# UltrasonicSensor.net
KiCad netlist of a schematic drawn in EAGLE
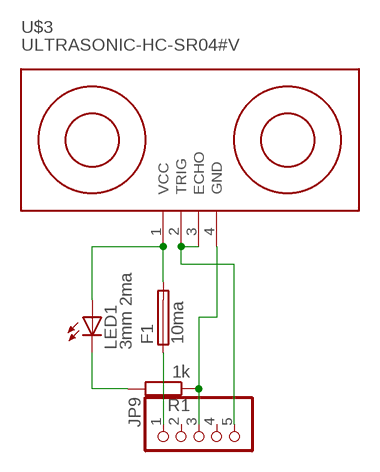
[diagram p0: schematic, sheet 1]

(export (version "E")
  (design (tool "Eeschema 10.0.6"))
  (components
    (comp (ref "F1")
      (value "10ma")
      (footprint "eagle-import:MF-SMDF050")
      (libsource (lib "eagle-import") (part "MF-SMDF050"))
    )
    (comp (ref "JP9")
      (value "PINHD-1X5")
      (footprint "eagle-import:1X05")
      (libsource (lib "eagle-import") (part "PINHD-1X5"))
    )
    (comp (ref "LED1")
      (value "3mm 2ma")
      (footprint "eagle-import:LED3MM")
      (fields (field (name "MF") "VISHAY SEMICONDUCTOR"))
      (libsource (lib "eagle-import") (part "TLLY4400"))
    )
    (comp (ref "R1")
      (value "1k")
      (footprint "eagle-import:M1206")
      (libsource (lib "eagle-import") (part "R-EU_M1206"))
    )
    (comp (ref "U$3")
      (value "ULTRASONIC-HC-SR04#V")
      (footprint "eagle-import:ULTRASONIC-HC-SR04#V")
      (libsource (lib "eagle-import") (part "ULTRASONIC-HC-SR04#V"))
    )
  )
  (nets
    (net (code "1") (name "Net-(F1-Pad1)") (class "Default")
      (node (ref "F1") (pin "1") (pinfunction "1_1") (pintype "passive"))
      (node (ref "JP9") (pin "1") (pinfunction "1_1") (pintype "passive"))
    )
    (net (code "2") (name "Net-(LED1-C)") (class "Default")
      (node (ref "LED1") (pin "K") (pinfunction "C_K") (pintype "passive"))
      (node (ref "R1") (pin "2") (pinfunction "2_2") (pintype "passive"))
    )
    (net (code "3") (name "Net-(U$3-ECHO)") (class "Default")
      (node (ref "JP9") (pin "5") (pinfunction "5_5") (pintype "passive"))
      (node (ref "U$3") (pin "2") (pinfunction "TRIG_2") (pintype "input"))
      (node (ref "U$3") (pin "3") (pinfunction "ECHO_3") (pintype "output"))
    )
    (net (code "4") (name "Net-(U$3-GND)") (class "Default")
      (node (ref "JP9") (pin "3") (pinfunction "3_3") (pintype "passive"))
      (node (ref "R1") (pin "1") (pinfunction "1_1") (pintype "passive"))
      (node (ref "U$3") (pin "4") (pinfunction "GND_4") (pintype "power_in"))
    )
    (net (code "5") (name "Net-(U$3-VCC)") (class "Default")
      (node (ref "F1") (pin "2") (pinfunction "2_2") (pintype "passive"))
      (node (ref "LED1") (pin "A") (pinfunction "A_A") (pintype "passive"))
      (node (ref "U$3") (pin "1") (pinfunction "VCC_1") (pintype "power_in"))
    )
    (net (code "6") (name "unconnected-(JP9-Pad2)") (class "Default")
      (node (ref "JP9") (pin "2") (pinfunction "2_2") (pintype "passive"))
    )
    (net (code "7") (name "unconnected-(JP9-Pad4)") (class "Default")
      (node (ref "JP9") (pin "4") (pinfunction "4_4") (pintype "passive"))
    )
  )
)
